# USB_OTG_FS.net
KiCad netlist of a schematic drawn in Altium Designer
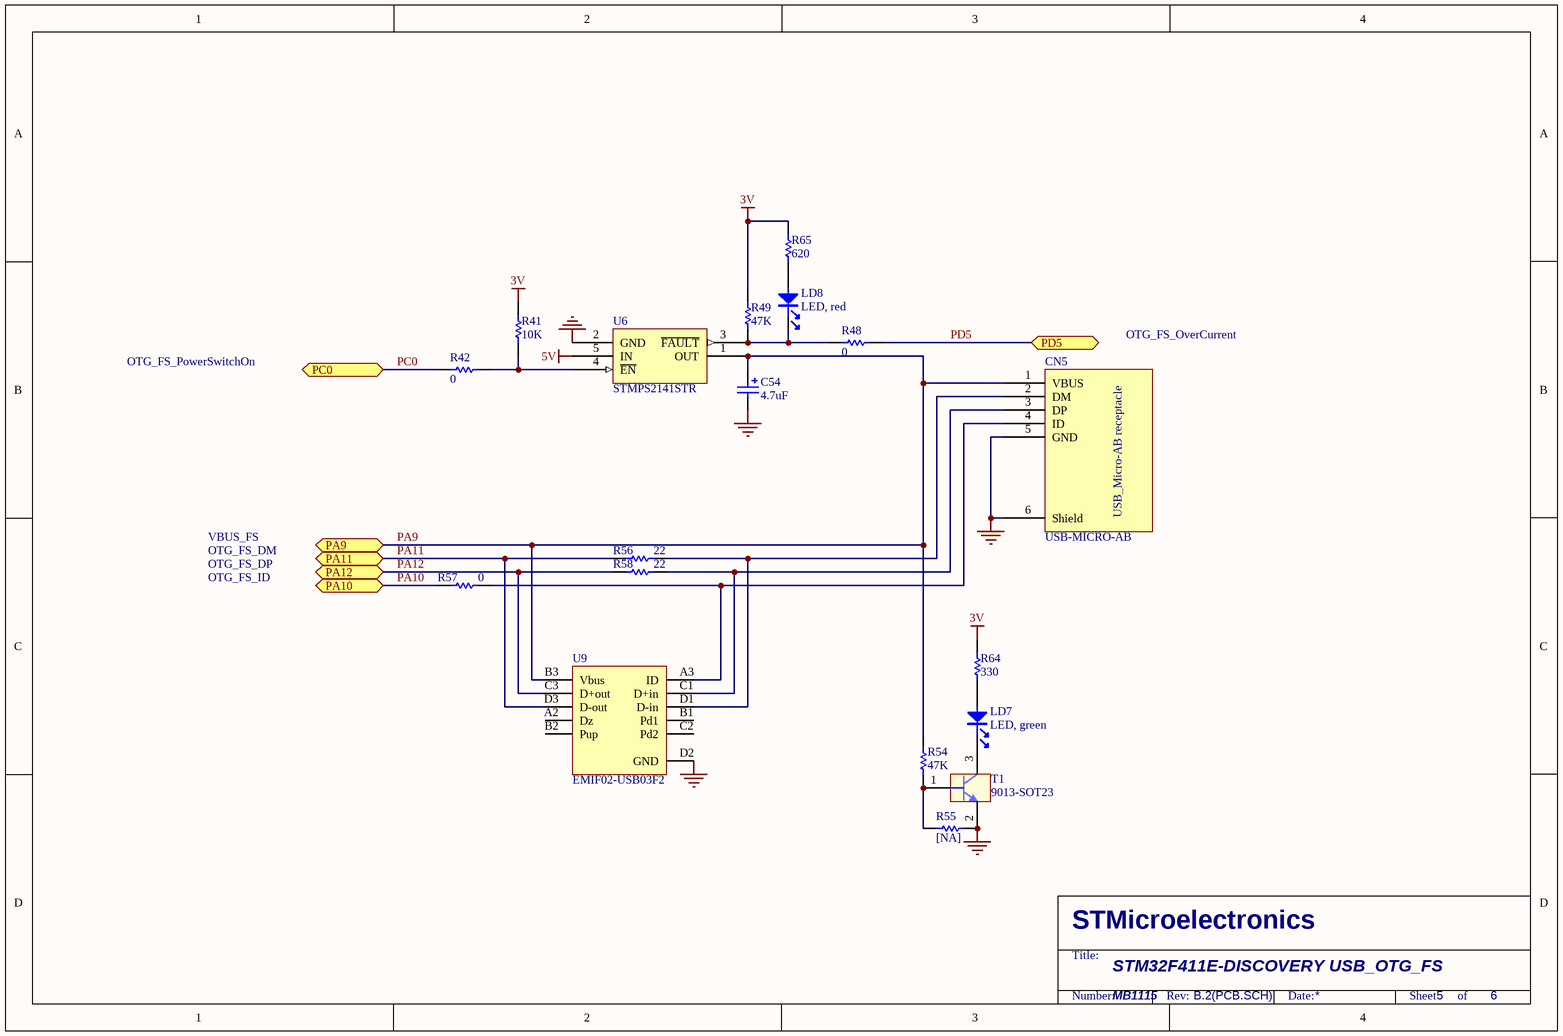
[diagram p0: USB_OTG_FS.SchDoc]

(export (version "E")
  (design (tool "Eeschema 10.0.6"))
  (components
    (comp (ref "C54")
      (value "4.7uF")
      (footprint "TAN-A")
      (description "Polarized Capacitor,4.7uF,16V,10%,typeA,AVX")
      (libsource (lib "MCD_TOOLS") (part "Cap_4.7uF_POL_10%_TANA"))
    )
    (comp (ref "CN5")
      (value "USB-MICRO-AB")
      (footprint "STM-SMEE:USB-MICRO-AB")
      (description "USB-MICRO-AB, 47590-0001, SMT, MOLEX")
      (libsource (lib "MCD_TOOLS") (part "USB-MICRO-AB"))
    )
    (comp (ref "LD7")
      (value "LED, green")
      (footprint "0603D")
      (description "LED,green,0603,19-213SYGC/S530-E2/TR8,everlight")
      (libsource (lib "MCD_TOOLS") (part "LED_green"))
    )
    (comp (ref "LD8")
      (value "LED, red")
      (footprint "0603D")
      (description "LED,red,0603,19-213-R6C-AP1Q2B/3T,everlight")
      (libsource (lib "MCD_TOOLS") (part "LED_red"))
    )
    (comp (ref "R41")
      (value "10K")
      (footprint "0402R")
      (description "Resistor")
      (fields (field (name "PUBLISHER") "Altium Limited"))
      (libsource (lib "Miscellaneous Devices") (part "res1"))
    )
    (comp (ref "R42")
      (value "0")
      (footprint "STM-SMEE:0402R")
      (description "Resistor,0,0402")
      (libsource (lib "MCD_TOOLS") (part "Res_0_0402"))
    )
    (comp (ref "R48")
      (value "0")
      (footprint "STM-SMEE:0402R")
      (description "Resistor,0,0402")
      (libsource (lib "MCD_TOOLS") (part "Res_0_0402"))
    )
    (comp (ref "R49")
      (value "47K")
      (footprint "0402R")
      (description "Resistor")
      (fields (field (name "PUBLISHER") "Altium Limited"))
      (libsource (lib "Miscellaneous Devices") (part "res1"))
    )
    (comp (ref "R54")
      (value "47K")
      (footprint "0402R")
      (description "Resistor")
      (fields (field (name "PUBLISHER") "Altium Limited"))
      (libsource (lib "Miscellaneous Devices") (part "res1"))
    )
    (comp (ref "R55")
      (value "[NA]")
      (footprint "STM-SMEE:0402R")
      (description "Resistor,[NA],0402")
      (libsource (lib "MCD_TOOLS") (part "Res_NA_0402"))
    )
    (comp (ref "R56")
      (value "22")
      (footprint "0402R")
      (description "Resistor")
      (fields (field (name "PUBLISHER") "Altium Limited"))
      (libsource (lib "Miscellaneous Devices") (part "Res1"))
    )
    (comp (ref "R57")
      (value "0")
      (footprint "STM-SMEE:0402R")
      (description "Resistor,0,0402")
      (libsource (lib "MCD_TOOLS") (part "Res_0_0402"))
    )
    (comp (ref "R58")
      (value "22")
      (footprint "0402R")
      (description "Resistor")
      (fields (field (name "PUBLISHER") "Altium Limited"))
      (libsource (lib "Miscellaneous Devices") (part "Res1"))
    )
    (comp (ref "R64")
      (value "330")
      (footprint "0603R")
      (description "Resistor")
      (fields (field (name "PUBLISHER") "Altium Limited"))
      (libsource (lib "Miscellaneous Devices") (part "res1"))
    )
    (comp (ref "R65")
      (value "620")
      (footprint "0603R")
      (description "Resistor")
      (fields (field (name "PUBLISHER") "Altium Limited"))
      (libsource (lib "Miscellaneous Devices") (part "Res1"))
    )
    (comp (ref "T1")
      (value "9013-SOT23")
      (footprint "SOT-23")
      (description "NPN Bipolar Transistor, SOT-23 Footprint")
      (libsource (lib "MCD_TOOLS") (part "9013-SOT23"))
    )
    (comp (ref "U6")
      (value "STMPS2141STR")
      (footprint "SOT23-5L")
      (description "Enhanced single channel power switches")
      (libsource (lib "MCD_TOOLS") (part "STMPS2141STR"))
    )
    (comp (ref "U9")
      (value "EMIF02-USB03F2")
      (footprint "STM-SMEE:Flip Chip")
      (description "2-line IPAD, EMI filter including ESD protection")
      (libsource (lib "MCD_TOOLS") (part "EMIF02-USB03F2"))
    )
  )
  (nets
    (net (code "1") (name "/PA9") (class "Default")
      (node (ref "C54") (pin "1") (pinfunction "1_1") (pintype "passive"))
      (node (ref "CN5") (pin "1") (pinfunction "VBUS_1") (pintype "passive"))
      (node (ref "R54") (pin "2") (pinfunction "2_2") (pintype "passive"))
      (node (ref "U6") (pin "1") (pinfunction "OUT_1") (pintype "passive"))
      (node (ref "U9") (pin "B3") (pinfunction "Vbus_B3") (pintype "passive"))
    )
    (net (code "2") (name "/PA10") (class "Default")
      (node (ref "R57") (pin "1") (pinfunction "1_1") (pintype "passive"))
    )
    (net (code "3") (name "/PA11") (class "Default")
      (node (ref "R56") (pin "2") (pinfunction "2_2") (pintype "passive"))
      (node (ref "U9") (pin "D3") (pinfunction "D-out_D3") (pintype "passive"))
    )
    (net (code "4") (name "/PA12") (class "Default")
      (node (ref "R58") (pin "2") (pinfunction "2_2") (pintype "passive"))
      (node (ref "U9") (pin "C3") (pinfunction "D+out_C3") (pintype "passive"))
    )
    (net (code "5") (name "/PC0") (class "Default")
      (node (ref "R42") (pin "1") (pinfunction "1_1") (pintype "passive"))
    )
    (net (code "6") (name "/PD5") (class "Default")
      (node (ref "R48") (pin "2") (pinfunction "2_2") (pintype "passive"))
    )
    (net (code "7") (name "3V") (class "Default")
      (node (ref "R41") (pin "1") (pinfunction "1_1") (pintype "passive"))
      (node (ref "R49") (pin "1") (pinfunction "1_1") (pintype "passive"))
      (node (ref "R64") (pin "2") (pinfunction "2_2") (pintype "passive"))
      (node (ref "R65") (pin "2") (pinfunction "2_2") (pintype "passive"))
    )
    (net (code "8") (name "5V") (class "Default")
      (node (ref "U6") (pin "5") (pinfunction "IN_5") (pintype "passive"))
    )
    (net (code "9") (name "GND") (class "Default")
      (node (ref "C54") (pin "2") (pinfunction "2_2") (pintype "passive"))
      (node (ref "CN5") (pin "5") (pinfunction "GND_5") (pintype "passive"))
      (node (ref "CN5") (pin "6") (pinfunction "Shield_6") (pintype "passive"))
      (node (ref "R55") (pin "2") (pinfunction "2_2") (pintype "passive"))
      (node (ref "T1") (pin "2") (pinfunction "E_2") (pintype "passive"))
      (node (ref "U6") (pin "2") (pinfunction "GND_2") (pintype "passive"))
      (node (ref "U9") (pin "D2") (pinfunction "GND_D2") (pintype "passive"))
    )
    (net (code "10") (name "Net-(CN5-DM)") (class "Default")
      (node (ref "CN5") (pin "2") (pinfunction "DM_2") (pintype "passive"))
      (node (ref "R56") (pin "1") (pinfunction "1_1") (pintype "passive"))
      (node (ref "U9") (pin "D1") (pinfunction "D-in_D1") (pintype "passive"))
    )
    (net (code "11") (name "Net-(CN5-DP)") (class "Default")
      (node (ref "CN5") (pin "3") (pinfunction "DP_3") (pintype "passive"))
      (node (ref "R58") (pin "1") (pinfunction "1_1") (pintype "passive"))
      (node (ref "U9") (pin "C1") (pinfunction "D+in_C1") (pintype "passive"))
    )
    (net (code "12") (name "Net-(CN5-ID)") (class "Default")
      (node (ref "CN5") (pin "4") (pinfunction "ID_4") (pintype "passive"))
      (node (ref "R57") (pin "2") (pinfunction "2_2") (pintype "passive"))
      (node (ref "U9") (pin "A3") (pinfunction "ID_A3") (pintype "passive"))
    )
    (net (code "13") (name "Net-(LD7-Pad1)") (class "Default")
      (node (ref "LD7") (pin "1") (pintype "passive"))
      (node (ref "R64") (pin "1") (pinfunction "1_1") (pintype "passive"))
    )
    (net (code "14") (name "Net-(LD8-Pad1)") (class "Default")
      (node (ref "LD8") (pin "1") (pintype "passive"))
      (node (ref "R65") (pin "1") (pinfunction "1_1") (pintype "passive"))
    )
    (net (code "15") (name "Net-(T1-B)") (class "Default")
      (node (ref "R54") (pin "1") (pinfunction "1_1") (pintype "passive"))
      (node (ref "R55") (pin "1") (pinfunction "1_1") (pintype "passive"))
      (node (ref "T1") (pin "1") (pinfunction "B_1") (pintype "passive"))
    )
    (net (code "16") (name "Net-(T1-C)") (class "Default")
      (node (ref "LD7") (pin "2") (pintype "passive"))
      (node (ref "T1") (pin "3") (pinfunction "C_3") (pintype "passive"))
    )
    (net (code "17") (name "Net-(U6-~{EN})") (class "Default")
      (node (ref "R41") (pin "2") (pinfunction "2_2") (pintype "passive"))
      (node (ref "R42") (pin "2") (pinfunction "2_2") (pintype "passive"))
      (node (ref "U6") (pin "4") (pinfunction "~{EN}_4") (pintype "input"))
    )
    (net (code "18") (name "Net-(U6-~{FAULT})") (class "Default")
      (node (ref "LD8") (pin "2") (pintype "passive"))
      (node (ref "R48") (pin "1") (pinfunction "1_1") (pintype "passive"))
      (node (ref "R49") (pin "2") (pinfunction "2_2") (pintype "passive"))
      (node (ref "U6") (pin "3") (pinfunction "~{FAULT}_3") (pintype "output"))
    )
    (net (code "19") (name "unconnected-(U9-Dz-PadA2)") (class "Default")
      (node (ref "U9") (pin "A2") (pinfunction "Dz_A2") (pintype "passive"))
    )
    (net (code "20") (name "unconnected-(U9-Pd1-PadB1)") (class "Default")
      (node (ref "U9") (pin "B1") (pinfunction "Pd1_B1") (pintype "passive"))
    )
    (net (code "21") (name "unconnected-(U9-Pd2-PadC2)") (class "Default")
      (node (ref "U9") (pin "C2") (pinfunction "Pd2_C2") (pintype "passive"))
    )
    (net (code "22") (name "unconnected-(U9-Pup-PadB2)") (class "Default")
      (node (ref "U9") (pin "B2") (pinfunction "Pup_B2") (pintype "passive"))
    )
  )
)
